# Dog_Fountain.net
KiCad netlist of a schematic drawn in EAGLE
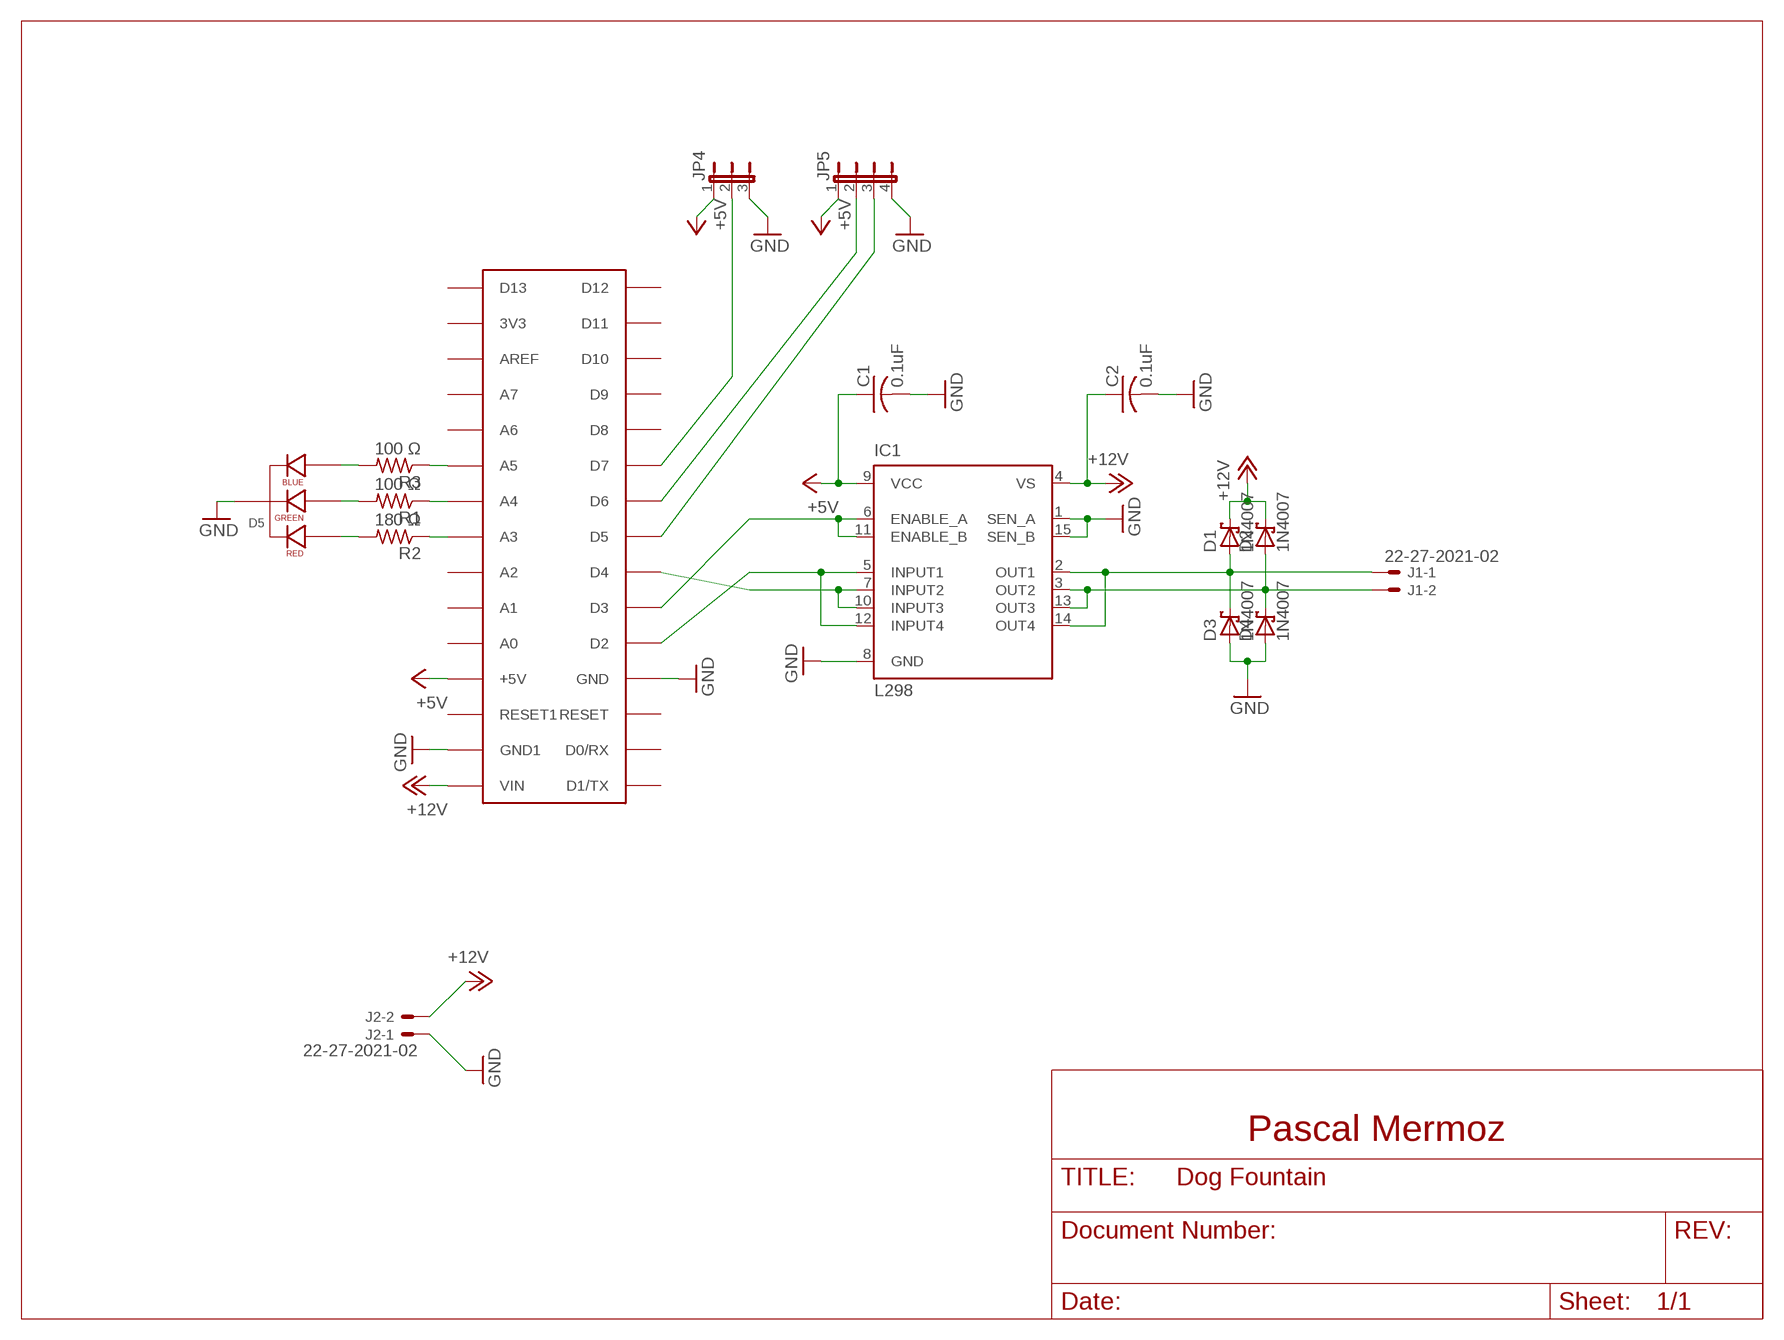
[diagram p0: schematic, sheet 1]

(export (version "E")
  (design (tool "Eeschema 10.0.6"))
  (components
    (comp (ref "C1")
      (value "0.1uF")
      (footprint "eagle-import:C050-024X044")
      (fields (field (name "MPN") "C317C104K5R5TA"))
      (libsource (lib "eagle-import") (part "C-US050-024X044"))
    )
    (comp (ref "C2")
      (value "0.1uF")
      (footprint "eagle-import:C050-024X044")
      (fields (field (name "MPN") "C317C104K5R5TA"))
      (libsource (lib "eagle-import") (part "C-US050-024X044"))
    )
    (comp (ref "D1")
      (value "1N4007")
      (footprint "eagle-import:DO41-7.6")
      (fields (field (name "MPN") "KBP202G"))
      (libsource (lib "eagle-import") (part "1N5818-B"))
    )
    (comp (ref "D2")
      (value "1N4007")
      (footprint "eagle-import:DO41-7.6")
      (fields (field (name "MPN") "KBP202G"))
      (libsource (lib "eagle-import") (part "1N5818-B"))
    )
    (comp (ref "D3")
      (value "1N4007")
      (footprint "eagle-import:DO41-7.6")
      (fields (field (name "MPN") "KBP202G"))
      (libsource (lib "eagle-import") (part "1N5818-B"))
    )
    (comp (ref "D4")
      (value "1N4007")
      (footprint "eagle-import:DO41-7.6")
      (fields (field (name "MPN") "KBP202G"))
      (libsource (lib "eagle-import") (part "1N5818-B"))
    )
    (comp (ref "D5")
      (value "LED-RGB-CC-THRUDIFFUSE")
      (footprint "eagle-import:LED-RGB-THRU")
      (libsource (lib "eagle-import") (part "LED-RGB-CC-THRUDIFFUSE"))
    )
    (comp (ref "IC1")
      (value "L298")
      (footprint "eagle-import:MULTIWATT-15")
      (fields (field (name "MPN") "L298N"))
      (libsource (lib "eagle-import") (part "L298"))
    )
    (comp (ref "J1")
      (value "22-27-2021-02")
      (footprint "eagle-import:6410-02")
      (libsource (lib "eagle-import") (part "22-?-0227-2021"))
    )
    (comp (ref "J2")
      (value "22-27-2021-02")
      (footprint "eagle-import:6410-02")
      (libsource (lib "eagle-import") (part "22-?-0227-2021"))
    )
    (comp (ref "JP4")
      (value "JP2E")
      (footprint "eagle-import:JP2")
      (libsource (lib "eagle-import") (part "JP2E"))
    )
    (comp (ref "JP5")
      (value "JP4E")
      (footprint "eagle-import:JP4")
      (libsource (lib "eagle-import") (part "JP4E"))
    )
    (comp (ref "R1")
      (value "100 Ω")
      (footprint "eagle-import:0204V")
      (libsource (lib "eagle-import") (part "R-US_0204/2V"))
    )
    (comp (ref "R2")
      (value "180 Ω")
      (footprint "eagle-import:0204V")
      (libsource (lib "eagle-import") (part "R-US_0204/2V"))
    )
    (comp (ref "R3")
      (value "100 Ω")
      (footprint "eagle-import:0204V")
      (libsource (lib "eagle-import") (part "R-US_0204/2V"))
    )
    (comp (ref "U$1")
      (value "ARDUINONANO")
      (footprint "eagle-import:PDIP-32")
      (fields (field (name "MPN") "A000005"))
      (libsource (lib "eagle-import") (part "ARDUINONANO"))
    )
  )
  (nets
    (net (code "1") (name "+5V") (class "Default")
      (node (ref "C1") (pin "1") (pinfunction "1_1") (pintype "passive"))
      (node (ref "IC1") (pin "9") (pinfunction "VCC_9") (pintype "power_in"))
      (node (ref "JP4") (pin "1") (pinfunction "1_1") (pintype "passive"))
      (node (ref "JP5") (pin "1") (pinfunction "1_1") (pintype "passive"))
      (node (ref "U$1") (pin "+5V") (pinfunction "+5V_+5V") (pintype "bidirectional"))
    )
    (net (code "2") (name "+12V") (class "Default")
      (node (ref "C2") (pin "1") (pinfunction "1_1") (pintype "passive"))
      (node (ref "D1") (pin "C") (pinfunction "C_C") (pintype "passive"))
      (node (ref "D2") (pin "C") (pinfunction "C_C") (pintype "passive"))
      (node (ref "IC1") (pin "4") (pinfunction "VS_4") (pintype "power_in"))
      (node (ref "J2") (pin "2") (pinfunction "S_2") (pintype "passive"))
      (node (ref "U$1") (pin "VIN") (pinfunction "VIN_VIN") (pintype "bidirectional"))
    )
    (net (code "3") (name "GND") (class "Default")
      (node (ref "C1") (pin "2") (pinfunction "2_2") (pintype "passive"))
      (node (ref "C2") (pin "2") (pinfunction "2_2") (pintype "passive"))
      (node (ref "D3") (pin "A") (pinfunction "A_A") (pintype "passive"))
      (node (ref "D4") (pin "A") (pinfunction "A_A") (pintype "passive"))
      (node (ref "D5") (pin "2") (pinfunction "CATHODE_2") (pintype "bidirectional"))
      (node (ref "IC1") (pin "1") (pinfunction "SEN_A_1") (pintype "input"))
      (node (ref "IC1") (pin "15") (pinfunction "SEN_B_15") (pintype "input"))
      (node (ref "IC1") (pin "8") (pinfunction "GND_8") (pintype "power_in"))
      (node (ref "J2") (pin "1") (pinfunction "S_1") (pintype "passive"))
      (node (ref "JP4") (pin "3") (pinfunction "3_3") (pintype "passive"))
      (node (ref "JP5") (pin "4") (pinfunction "4_4") (pintype "passive"))
      (node (ref "U$1") (pin "GND") (pinfunction "GND_GND") (pintype "bidirectional"))
      (node (ref "U$1") (pin "GND1") (pinfunction "GND1_GND1") (pintype "bidirectional"))
    )
    (net (code "4") (name "Net-(D5-BLUE_CATHODE)") (class "Default")
      (node (ref "D5") (pin "4") (pinfunction "BLUE_CATHODE_4") (pintype "bidirectional"))
      (node (ref "R3") (pin "2") (pinfunction "2_2") (pintype "passive"))
    )
    (net (code "5") (name "Net-(D5-GREEN_CATHODE)") (class "Default")
      (node (ref "D5") (pin "3") (pinfunction "GREEN_CATHODE_3") (pintype "bidirectional"))
      (node (ref "R1") (pin "2") (pinfunction "2_2") (pintype "passive"))
    )
    (net (code "6") (name "Net-(D5-RED_CATHODE)") (class "Default")
      (node (ref "D5") (pin "1") (pinfunction "RED_CATHODE_1") (pintype "bidirectional"))
      (node (ref "R2") (pin "2") (pinfunction "2_2") (pintype "passive"))
    )
    (net (code "7") (name "Net-(IC1-ENABLE_A)") (class "Default")
      (node (ref "IC1") (pin "11") (pinfunction "ENABLE_B_11") (pintype "input"))
      (node (ref "IC1") (pin "6") (pinfunction "ENABLE_A_6") (pintype "input"))
      (node (ref "U$1") (pin "D3") (pinfunction "D3_D3") (pintype "bidirectional"))
    )
    (net (code "8") (name "Net-(IC1-INPUT1)") (class "Default")
      (node (ref "IC1") (pin "12") (pinfunction "INPUT4_12") (pintype "input"))
      (node (ref "IC1") (pin "5") (pinfunction "INPUT1_5") (pintype "input"))
      (node (ref "U$1") (pin "D2") (pinfunction "D2_D2") (pintype "bidirectional"))
    )
    (net (code "9") (name "Net-(IC1-INPUT2)") (class "Default")
      (node (ref "IC1") (pin "10") (pinfunction "INPUT3_10") (pintype "input"))
      (node (ref "IC1") (pin "7") (pinfunction "INPUT2_7") (pintype "input"))
      (node (ref "U$1") (pin "D4") (pinfunction "D4_D4") (pintype "bidirectional"))
    )
    (net (code "10") (name "Net-(IC1-OUT1)") (class "Default")
      (node (ref "D1") (pin "A") (pinfunction "A_A") (pintype "passive"))
      (node (ref "D3") (pin "C") (pinfunction "C_C") (pintype "passive"))
      (node (ref "IC1") (pin "14") (pinfunction "OUT4_14") (pintype "output"))
      (node (ref "IC1") (pin "2") (pinfunction "OUT1_2") (pintype "output"))
      (node (ref "J1") (pin "1") (pinfunction "S_1") (pintype "passive"))
    )
    (net (code "11") (name "Net-(IC1-OUT2)") (class "Default")
      (node (ref "D2") (pin "A") (pinfunction "A_A") (pintype "passive"))
      (node (ref "D4") (pin "C") (pinfunction "C_C") (pintype "passive"))
      (node (ref "IC1") (pin "13") (pinfunction "OUT3_13") (pintype "output"))
      (node (ref "IC1") (pin "3") (pinfunction "OUT2_3") (pintype "output"))
      (node (ref "J1") (pin "2") (pinfunction "S_2") (pintype "passive"))
    )
    (net (code "12") (name "Net-(JP4-Pad2)") (class "Default")
      (node (ref "JP4") (pin "2") (pinfunction "2_2") (pintype "passive"))
      (node (ref "U$1") (pin "D7") (pinfunction "D7_D7") (pintype "bidirectional"))
    )
    (net (code "13") (name "Net-(JP5-Pad2)") (class "Default")
      (node (ref "JP5") (pin "2") (pinfunction "2_2") (pintype "passive"))
      (node (ref "U$1") (pin "D6") (pinfunction "D6_D6") (pintype "bidirectional"))
    )
    (net (code "14") (name "Net-(JP5-Pad3)") (class "Default")
      (node (ref "JP5") (pin "3") (pinfunction "3_3") (pintype "passive"))
      (node (ref "U$1") (pin "D5") (pinfunction "D5_D5") (pintype "bidirectional"))
    )
    (net (code "15") (name "Net-(R1-Pad1)") (class "Default")
      (node (ref "R1") (pin "1") (pinfunction "1_1") (pintype "passive"))
      (node (ref "U$1") (pin "A4") (pinfunction "A4_A4") (pintype "bidirectional"))
    )
    (net (code "16") (name "Net-(R2-Pad1)") (class "Default")
      (node (ref "R2") (pin "1") (pinfunction "1_1") (pintype "passive"))
      (node (ref "U$1") (pin "A3") (pinfunction "A3_A3") (pintype "bidirectional"))
    )
    (net (code "17") (name "Net-(R3-Pad1)") (class "Default")
      (node (ref "R3") (pin "1") (pinfunction "1_1") (pintype "passive"))
      (node (ref "U$1") (pin "A5") (pinfunction "A5_A5") (pintype "bidirectional"))
    )
    (net (code "18") (name "unconnected-(U$1-Pad3V3)") (class "Default")
      (node (ref "U$1") (pin "3V3") (pinfunction "3V3_3V3") (pintype "bidirectional"))
    )
    (net (code "19") (name "unconnected-(U$1-PadA0)") (class "Default")
      (node (ref "U$1") (pin "A0") (pinfunction "A0_A0") (pintype "bidirectional"))
    )
    (net (code "20") (name "unconnected-(U$1-PadA1)") (class "Default")
      (node (ref "U$1") (pin "A1") (pinfunction "A1_A1") (pintype "bidirectional"))
    )
    (net (code "21") (name "unconnected-(U$1-PadA2)") (class "Default")
      (node (ref "U$1") (pin "A2") (pinfunction "A2_A2") (pintype "bidirectional"))
    )
    (net (code "22") (name "unconnected-(U$1-PadA6)") (class "Default")
      (node (ref "U$1") (pin "A6") (pinfunction "A6_A6") (pintype "bidirectional"))
    )
    (net (code "23") (name "unconnected-(U$1-PadA7)") (class "Default")
      (node (ref "U$1") (pin "A7") (pinfunction "A7_A7") (pintype "bidirectional"))
    )
    (net (code "24") (name "unconnected-(U$1-PadAREF)") (class "Default")
      (node (ref "U$1") (pin "AREF") (pinfunction "AREF_AREF") (pintype "bidirectional"))
    )
    (net (code "25") (name "unconnected-(U$1-PadD0{slash}RX)") (class "Default")
      (node (ref "U$1") (pin "D0/RX") (pinfunction "D0/RX_D0/RX") (pintype "bidirectional"))
    )
    (net (code "26") (name "unconnected-(U$1-PadD1{slash}TX)") (class "Default")
      (node (ref "U$1") (pin "D1/TX") (pinfunction "D1/TX_D1/TX") (pintype "bidirectional"))
    )
    (net (code "27") (name "unconnected-(U$1-PadD8)") (class "Default")
      (node (ref "U$1") (pin "D8") (pinfunction "D8_D8") (pintype "bidirectional"))
    )
    (net (code "28") (name "unconnected-(U$1-PadD9)") (class "Default")
      (node (ref "U$1") (pin "D9") (pinfunction "D9_D9") (pintype "bidirectional"))
    )
    (net (code "29") (name "unconnected-(U$1-PadD10)") (class "Default")
      (node (ref "U$1") (pin "D10") (pinfunction "D10_D10") (pintype "bidirectional"))
    )
    (net (code "30") (name "unconnected-(U$1-PadD11)") (class "Default")
      (node (ref "U$1") (pin "D11") (pinfunction "D11_D11") (pintype "bidirectional"))
    )
    (net (code "31") (name "unconnected-(U$1-PadD12)") (class "Default")
      (node (ref "U$1") (pin "D12") (pinfunction "D12_D12") (pintype "bidirectional"))
    )
    (net (code "32") (name "unconnected-(U$1-PadD13)") (class "Default")
      (node (ref "U$1") (pin "D13") (pinfunction "D13_D13") (pintype "bidirectional"))
    )
    (net (code "33") (name "unconnected-(U$1-PadRESET)") (class "Default")
      (node (ref "U$1") (pin "RESET") (pinfunction "RESET_RESET") (pintype "bidirectional"))
    )
    (net (code "34") (name "unconnected-(U$1-PadRESET1)") (class "Default")
      (node (ref "U$1") (pin "RESET1") (pinfunction "RESET1_RESET1") (pintype "bidirectional"))
    )
  )
)
